# fpga-bank6-outside.net
KiCad netlist of a schematic drawn in Altium Designer
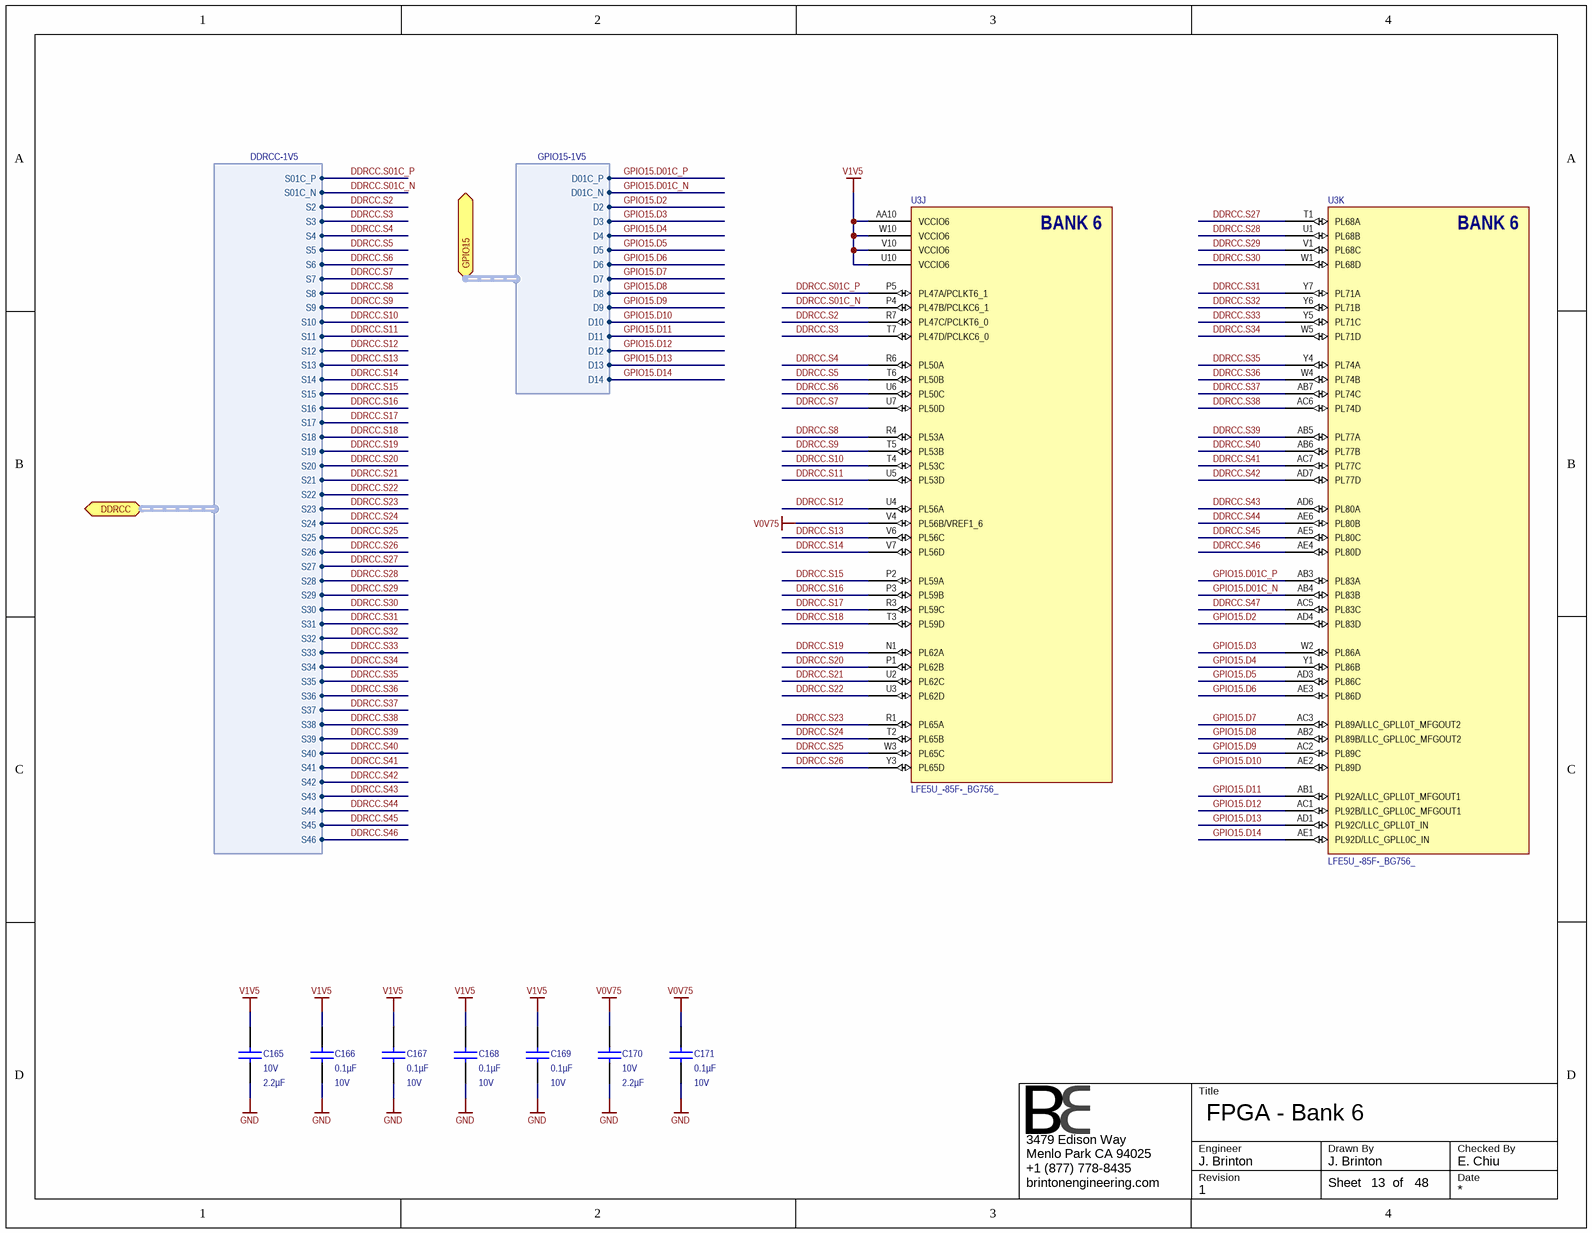
[diagram p0: fpga-bank6-outside.SchDoc]

(export (version "E")
  (design (tool "Eeschema 10.0.6"))
  (components
    (comp (ref "C165")
      (value "GRM188R71A225KE15D")
      (footprint "CAPC1608X90N")
      (description "CAP CER 2.2UF 10V 10% X7R 0603")
      (fields
        (field (name "MANUFACTURER") "Murata Electronics North America")
        (field (name "TOLERANCE") "±10%")
        (field (name "VOLTAGE - RATED") "10V")
        (field (name "CAPACITANCE") "2.2µF")
      )
      (libsource (lib "murata") (part "GRM188R71A225KE15D"))
    )
    (comp (ref "C166")
      (value "GRM155R71A104KA01J")
      (footprint "CAPC1005X56N")
      (description "CAP CER 0.1UF 10V 10% X7R 0402")
      (fields
        (field (name "MANUFACTURER") "Murata Electronics North America")
        (field (name "TOLERANCE") "±10%")
        (field (name "CAPACITANCE") "0.1µF")
        (field (name "VOLTAGE - RATED") "10V")
      )
      (libsource (lib "murata") (part "GRM155R71A104KA01J"))
    )
    (comp (ref "C167")
      (value "GRM155R71A104KA01J")
      (footprint "CAPC1005X56N")
      (description "CAP CER 0.1UF 10V 10% X7R 0402")
      (fields
        (field (name "MANUFACTURER") "Murata Electronics North America")
        (field (name "TOLERANCE") "±10%")
        (field (name "CAPACITANCE") "0.1µF")
        (field (name "VOLTAGE - RATED") "10V")
      )
      (libsource (lib "murata") (part "GRM155R71A104KA01J"))
    )
    (comp (ref "C168")
      (value "GRM155R71A104KA01J")
      (footprint "CAPC1005X56N")
      (description "CAP CER 0.1UF 10V 10% X7R 0402")
      (fields
        (field (name "MANUFACTURER") "Murata Electronics North America")
        (field (name "TOLERANCE") "±10%")
        (field (name "CAPACITANCE") "0.1µF")
        (field (name "VOLTAGE - RATED") "10V")
      )
      (libsource (lib "murata") (part "GRM155R71A104KA01J"))
    )
    (comp (ref "C169")
      (value "GRM155R71A104KA01J")
      (footprint "CAPC1005X56N")
      (description "CAP CER 0.1UF 10V 10% X7R 0402")
      (fields
        (field (name "MANUFACTURER") "Murata Electronics North America")
        (field (name "TOLERANCE") "±10%")
        (field (name "CAPACITANCE") "0.1µF")
        (field (name "VOLTAGE - RATED") "10V")
      )
      (libsource (lib "murata") (part "GRM155R71A104KA01J"))
    )
    (comp (ref "C170")
      (value "GRM188R71A225KE15D")
      (footprint "CAPC1608X90N")
      (description "CAP CER 2.2UF 10V 10% X7R 0603")
      (fields
        (field (name "MANUFACTURER") "Murata Electronics North America")
        (field (name "TOLERANCE") "±10%")
        (field (name "VOLTAGE - RATED") "10V")
        (field (name "CAPACITANCE") "2.2µF")
      )
      (libsource (lib "murata") (part "GRM188R71A225KE15D"))
    )
    (comp (ref "C171")
      (value "GRM155R71A104KA01J")
      (footprint "CAPC1005X56N")
      (description "CAP CER 0.1UF 10V 10% X7R 0402")
      (fields
        (field (name "MANUFACTURER") "Murata Electronics North America")
        (field (name "TOLERANCE") "±10%")
        (field (name "CAPACITANCE") "0.1µF")
        (field (name "VOLTAGE - RATED") "10V")
      )
      (libsource (lib "murata") (part "GRM155R71A104KA01J"))
    )
    (comp (ref "U3")
      (value "LFE5U_-85F-_BG756_")
      (footprint "lattice:caBGA756")
      (description "ECP5 FPGA, 85k LUT, 756-caBGA")
      (fields (field (name "MANUFACTURER") "Lattice Semiconductor"))
      (libsource (lib "lattice") (part "LFE5U_-85F-_BG756_"))
    )
  )
  (nets
    (net (code "3") (name "/DDRCC.S01C_N") (class "Default")
      (node (ref "U3") (pin "P4") (pinfunction "PL47B/PCLKC6_1_P4") (pintype "bidirectional"))
    )
    (net (code "4") (name "/DDRCC.S01C_P") (class "Default")
      (node (ref "U3") (pin "P5") (pinfunction "PL47A/PCLKT6_1_P5") (pintype "bidirectional"))
    )
    (net (code "5") (name "/DDRCC.S2") (class "Default")
      (node (ref "U3") (pin "R7") (pinfunction "PL47C/PCLKT6_0_R7") (pintype "bidirectional"))
    )
    (net (code "6") (name "/DDRCC.S3") (class "Default")
      (node (ref "U3") (pin "T7") (pinfunction "PL47D/PCLKC6_0_T7") (pintype "bidirectional"))
    )
    (net (code "7") (name "/DDRCC.S4") (class "Default")
      (node (ref "U3") (pin "R6") (pinfunction "PL50A_R6") (pintype "bidirectional"))
    )
    (net (code "8") (name "/DDRCC.S5") (class "Default")
      (node (ref "U3") (pin "T6") (pinfunction "PL50B_T6") (pintype "bidirectional"))
    )
    (net (code "9") (name "/DDRCC.S6") (class "Default")
      (node (ref "U3") (pin "U6") (pinfunction "PL50C_U6") (pintype "bidirectional"))
    )
    (net (code "10") (name "/DDRCC.S7") (class "Default")
      (node (ref "U3") (pin "U7") (pinfunction "PL50D_U7") (pintype "bidirectional"))
    )
    (net (code "11") (name "/DDRCC.S8") (class "Default")
      (node (ref "U3") (pin "R4") (pinfunction "PL53A_R4") (pintype "bidirectional"))
    )
    (net (code "12") (name "/DDRCC.S9") (class "Default")
      (node (ref "U3") (pin "T5") (pinfunction "PL53B_T5") (pintype "bidirectional"))
    )
    (net (code "13") (name "/DDRCC.S10") (class "Default")
      (node (ref "U3") (pin "T4") (pinfunction "PL53C_T4") (pintype "bidirectional"))
    )
    (net (code "14") (name "/DDRCC.S11") (class "Default")
      (node (ref "U3") (pin "U5") (pinfunction "PL53D_U5") (pintype "bidirectional"))
    )
    (net (code "15") (name "/DDRCC.S12") (class "Default")
      (node (ref "U3") (pin "U4") (pinfunction "PL56A_U4") (pintype "bidirectional"))
    )
    (net (code "16") (name "/DDRCC.S13") (class "Default")
      (node (ref "U3") (pin "V6") (pinfunction "PL56C_V6") (pintype "bidirectional"))
    )
    (net (code "17") (name "/DDRCC.S14") (class "Default")
      (node (ref "U3") (pin "V7") (pinfunction "PL56D_V7") (pintype "bidirectional"))
    )
    (net (code "18") (name "/DDRCC.S15") (class "Default")
      (node (ref "U3") (pin "P2") (pinfunction "PL59A_P2") (pintype "bidirectional"))
    )
    (net (code "19") (name "/DDRCC.S16") (class "Default")
      (node (ref "U3") (pin "P3") (pinfunction "PL59B_P3") (pintype "bidirectional"))
    )
    (net (code "20") (name "/DDRCC.S17") (class "Default")
      (node (ref "U3") (pin "R3") (pinfunction "PL59C_R3") (pintype "bidirectional"))
    )
    (net (code "21") (name "/DDRCC.S18") (class "Default")
      (node (ref "U3") (pin "T3") (pinfunction "PL59D_T3") (pintype "bidirectional"))
    )
    (net (code "22") (name "/DDRCC.S19") (class "Default")
      (node (ref "U3") (pin "N1") (pinfunction "PL62A_N1") (pintype "bidirectional"))
    )
    (net (code "23") (name "/DDRCC.S20") (class "Default")
      (node (ref "U3") (pin "P1") (pinfunction "PL62B_P1") (pintype "bidirectional"))
    )
    (net (code "24") (name "/DDRCC.S21") (class "Default")
      (node (ref "U3") (pin "U2") (pinfunction "PL62C_U2") (pintype "bidirectional"))
    )
    (net (code "25") (name "/DDRCC.S22") (class "Default")
      (node (ref "U3") (pin "U3") (pinfunction "PL62D_U3") (pintype "bidirectional"))
    )
    (net (code "26") (name "/DDRCC.S23") (class "Default")
      (node (ref "U3") (pin "R1") (pinfunction "PL65A_R1") (pintype "bidirectional"))
    )
    (net (code "27") (name "/DDRCC.S24") (class "Default")
      (node (ref "U3") (pin "T2") (pinfunction "PL65B_T2") (pintype "bidirectional"))
    )
    (net (code "28") (name "/DDRCC.S25") (class "Default")
      (node (ref "U3") (pin "W3") (pinfunction "PL65C_W3") (pintype "bidirectional"))
    )
    (net (code "29") (name "/DDRCC.S26") (class "Default")
      (node (ref "U3") (pin "Y3") (pinfunction "PL65D_Y3") (pintype "bidirectional"))
    )
    (net (code "30") (name "/DDRCC.S27") (class "Default")
      (node (ref "U3") (pin "T1") (pinfunction "PL68A_T1") (pintype "bidirectional"))
    )
    (net (code "31") (name "/DDRCC.S28") (class "Default")
      (node (ref "U3") (pin "U1") (pinfunction "PL68B_U1") (pintype "bidirectional"))
    )
    (net (code "32") (name "/DDRCC.S29") (class "Default")
      (node (ref "U3") (pin "V1") (pinfunction "PL68C_V1") (pintype "bidirectional"))
    )
    (net (code "33") (name "/DDRCC.S30") (class "Default")
      (node (ref "U3") (pin "W1") (pinfunction "PL68D_W1") (pintype "bidirectional"))
    )
    (net (code "34") (name "/DDRCC.S31") (class "Default")
      (node (ref "U3") (pin "Y7") (pinfunction "PL71A_Y7") (pintype "bidirectional"))
    )
    (net (code "35") (name "/DDRCC.S32") (class "Default")
      (node (ref "U3") (pin "Y6") (pinfunction "PL71B_Y6") (pintype "bidirectional"))
    )
    (net (code "36") (name "/DDRCC.S33") (class "Default")
      (node (ref "U3") (pin "Y5") (pinfunction "PL71C_Y5") (pintype "bidirectional"))
    )
    (net (code "37") (name "/DDRCC.S34") (class "Default")
      (node (ref "U3") (pin "W5") (pinfunction "PL71D_W5") (pintype "bidirectional"))
    )
    (net (code "38") (name "/DDRCC.S35") (class "Default")
      (node (ref "U3") (pin "Y4") (pinfunction "PL74A_Y4") (pintype "bidirectional"))
    )
    (net (code "39") (name "/DDRCC.S36") (class "Default")
      (node (ref "U3") (pin "W4") (pinfunction "PL74B_W4") (pintype "bidirectional"))
    )
    (net (code "40") (name "/DDRCC.S37") (class "Default")
      (node (ref "U3") (pin "AB7") (pinfunction "PL74C_AB7") (pintype "bidirectional"))
    )
    (net (code "41") (name "/DDRCC.S38") (class "Default")
      (node (ref "U3") (pin "AC6") (pinfunction "PL74D_AC6") (pintype "bidirectional"))
    )
    (net (code "42") (name "/DDRCC.S39") (class "Default")
      (node (ref "U3") (pin "AB5") (pinfunction "PL77A_AB5") (pintype "bidirectional"))
    )
    (net (code "43") (name "/DDRCC.S40") (class "Default")
      (node (ref "U3") (pin "AB6") (pinfunction "PL77B_AB6") (pintype "bidirectional"))
    )
    (net (code "44") (name "/DDRCC.S41") (class "Default")
      (node (ref "U3") (pin "AC7") (pinfunction "PL77C_AC7") (pintype "bidirectional"))
    )
    (net (code "45") (name "/DDRCC.S42") (class "Default")
      (node (ref "U3") (pin "AD7") (pinfunction "PL77D_AD7") (pintype "bidirectional"))
    )
    (net (code "46") (name "/DDRCC.S43") (class "Default")
      (node (ref "U3") (pin "AD6") (pinfunction "PL80A_AD6") (pintype "bidirectional"))
    )
    (net (code "47") (name "/DDRCC.S44") (class "Default")
      (node (ref "U3") (pin "AE6") (pinfunction "PL80B_AE6") (pintype "bidirectional"))
    )
    (net (code "48") (name "/DDRCC.S45") (class "Default")
      (node (ref "U3") (pin "AE5") (pinfunction "PL80C_AE5") (pintype "bidirectional"))
    )
    (net (code "49") (name "/DDRCC.S46") (class "Default")
      (node (ref "U3") (pin "AE4") (pinfunction "PL80D_AE4") (pintype "bidirectional"))
    )
    (net (code "50") (name "/DDRCC.S47") (class "Default")
      (node (ref "U3") (pin "AC5") (pinfunction "PL83C_AC5") (pintype "bidirectional"))
    )
    (net (code "51") (name "/GPIO15.D01C_N") (class "Default")
      (node (ref "U3") (pin "AB4") (pinfunction "PL83B_AB4") (pintype "bidirectional"))
    )
    (net (code "52") (name "/GPIO15.D01C_P") (class "Default")
      (node (ref "U3") (pin "AB3") (pinfunction "PL83A_AB3") (pintype "bidirectional"))
    )
    (net (code "53") (name "/GPIO15.D2") (class "Default")
      (node (ref "U3") (pin "AD4") (pinfunction "PL83D_AD4") (pintype "bidirectional"))
    )
    (net (code "54") (name "/GPIO15.D3") (class "Default")
      (node (ref "U3") (pin "W2") (pinfunction "PL86A_W2") (pintype "bidirectional"))
    )
    (net (code "55") (name "/GPIO15.D4") (class "Default")
      (node (ref "U3") (pin "Y1") (pinfunction "PL86B_Y1") (pintype "bidirectional"))
    )
    (net (code "56") (name "/GPIO15.D5") (class "Default")
      (node (ref "U3") (pin "AD3") (pinfunction "PL86C_AD3") (pintype "bidirectional"))
    )
    (net (code "57") (name "/GPIO15.D6") (class "Default")
      (node (ref "U3") (pin "AE3") (pinfunction "PL86D_AE3") (pintype "bidirectional"))
    )
    (net (code "58") (name "/GPIO15.D7") (class "Default")
      (node (ref "U3") (pin "AC3") (pinfunction "PL89A/LLC_GPLL0T_MFGOUT2_AC3") (pintype "bidirectional"))
    )
    (net (code "59") (name "/GPIO15.D8") (class "Default")
      (node (ref "U3") (pin "AB2") (pinfunction "PL89B/LLC_GPLL0C_MFGOUT2_AB2") (pintype "bidirectional"))
    )
    (net (code "60") (name "/GPIO15.D9") (class "Default")
      (node (ref "U3") (pin "AC2") (pinfunction "PL89C_AC2") (pintype "bidirectional"))
    )
    (net (code "61") (name "/GPIO15.D10") (class "Default")
      (node (ref "U3") (pin "AE2") (pinfunction "PL89D_AE2") (pintype "bidirectional"))
    )
    (net (code "62") (name "/GPIO15.D11") (class "Default")
      (node (ref "U3") (pin "AB1") (pinfunction "PL92A/LLC_GPLL0T_MFGOUT1_AB1") (pintype "bidirectional"))
    )
    (net (code "63") (name "/GPIO15.D12") (class "Default")
      (node (ref "U3") (pin "AC1") (pinfunction "PL92B/LLC_GPLL0C_MFGOUT1_AC1") (pintype "bidirectional"))
    )
    (net (code "64") (name "/GPIO15.D13") (class "Default")
      (node (ref "U3") (pin "AD1") (pinfunction "PL92C/LLC_GPLL0T_IN_AD1") (pintype "bidirectional"))
    )
    (net (code "65") (name "/GPIO15.D14") (class "Default")
      (node (ref "U3") (pin "AE1") (pinfunction "PL92D/LLC_GPLL0C_IN_AE1") (pintype "bidirectional"))
    )
    (net (code "68") (name "GND") (class "Default")
      (node (ref "C165") (pin "1") (pinfunction "1_1") (pintype "passive"))
      (node (ref "C166") (pin "1") (pinfunction "1_1") (pintype "passive"))
      (node (ref "C167") (pin "1") (pinfunction "1_1") (pintype "passive"))
      (node (ref "C168") (pin "1") (pinfunction "1_1") (pintype "passive"))
      (node (ref "C169") (pin "1") (pinfunction "1_1") (pintype "passive"))
      (node (ref "C170") (pin "1") (pinfunction "1_1") (pintype "passive"))
      (node (ref "C171") (pin "1") (pinfunction "1_1") (pintype "passive"))
    )
    (net (code "69") (name "V0V75") (class "Default")
      (node (ref "C170") (pin "2") (pinfunction "2_2") (pintype "passive"))
      (node (ref "C171") (pin "2") (pinfunction "2_2") (pintype "passive"))
      (node (ref "U3") (pin "V4") (pinfunction "PL56B/VREF1_6_V4") (pintype "bidirectional"))
    )
    (net (code "70") (name "V1V5") (class "Default")
      (node (ref "C165") (pin "2") (pinfunction "2_2") (pintype "passive"))
      (node (ref "C166") (pin "2") (pinfunction "2_2") (pintype "passive"))
      (node (ref "C167") (pin "2") (pinfunction "2_2") (pintype "passive"))
      (node (ref "C168") (pin "2") (pinfunction "2_2") (pintype "passive"))
      (node (ref "C169") (pin "2") (pinfunction "2_2") (pintype "passive"))
      (node (ref "U3") (pin "AA10") (pinfunction "VCCIO6_AA10") (pintype "power_in"))
      (node (ref "U3") (pin "U10") (pinfunction "VCCIO6_U10") (pintype "power_in"))
      (node (ref "U3") (pin "V10") (pinfunction "VCCIO6_V10") (pintype "power_in"))
      (node (ref "U3") (pin "W10") (pinfunction "VCCIO6_W10") (pintype "power_in"))
    )
  )
)
